# ModularLight.net
KiCad netlist of a schematic drawn in EAGLE
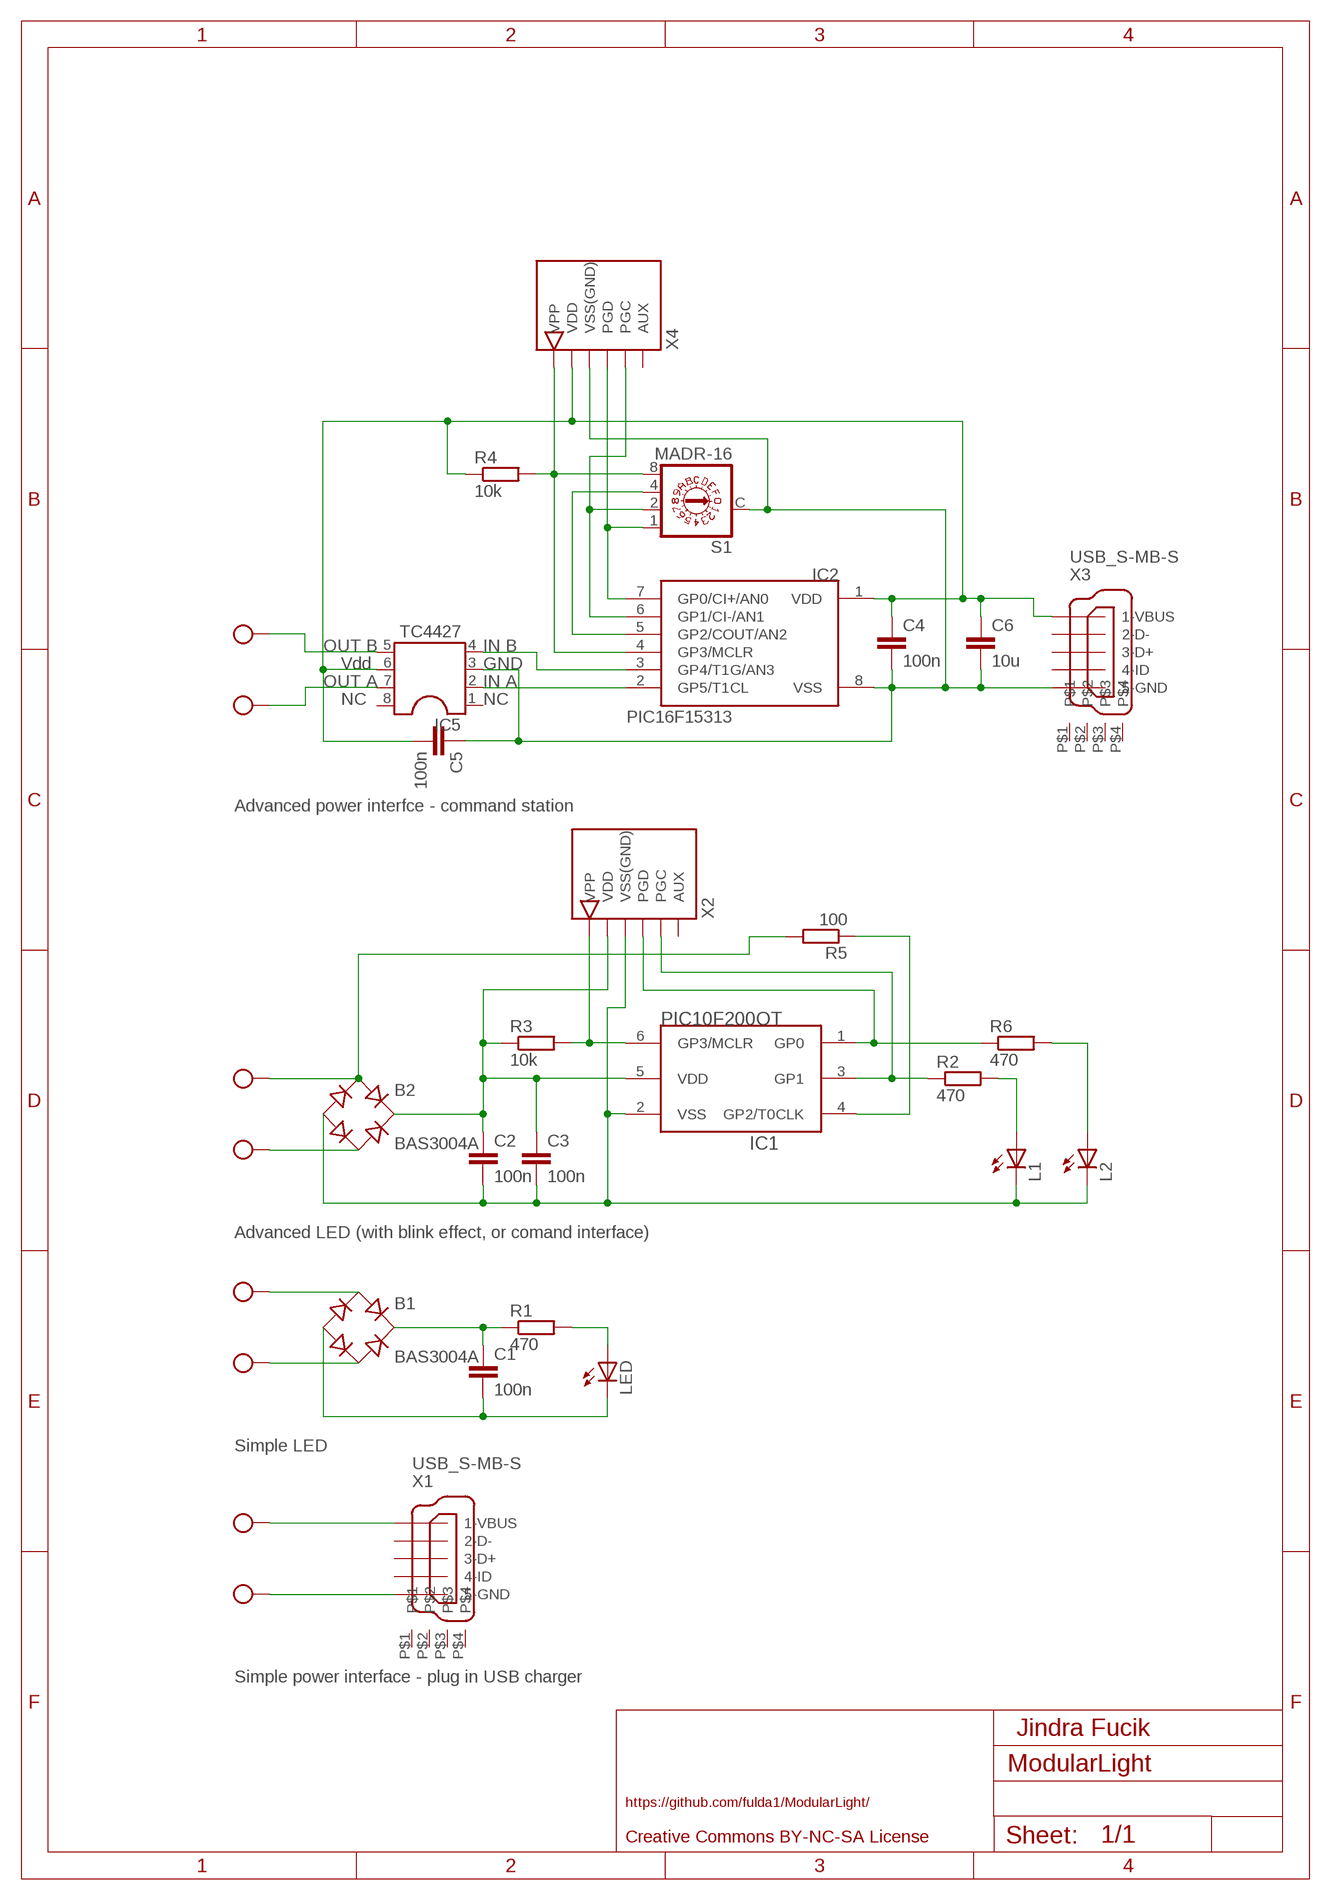
[diagram p0: schematic, sheet 1]

(export (version "E")
  (design (tool "Eeschema 10.0.6"))
  (components
    (comp (ref "B1")
      (value "BAS3004A")
      (footprint "eagle-import:SOT143")
      (libsource (lib "eagle-import") (part "RECTIFIER-SOT143"))
    )
    (comp (ref "B2")
      (value "BAS3004A")
      (footprint "eagle-import:SOT143")
      (libsource (lib "eagle-import") (part "RECTIFIER-SOT143"))
    )
    (comp (ref "C1")
      (value "100n")
      (footprint "eagle-import:C0805")
      (libsource (lib "eagle-import") (part "C-EUC0805"))
    )
    (comp (ref "C2")
      (value "100n")
      (footprint "eagle-import:C0805")
      (libsource (lib "eagle-import") (part "C-EUC0805"))
    )
    (comp (ref "C3")
      (value "100n")
      (footprint "eagle-import:C0805")
      (libsource (lib "eagle-import") (part "C-EUC0805"))
    )
    (comp (ref "C4")
      (value "100n")
      (footprint "eagle-import:C0805")
      (libsource (lib "eagle-import") (part "C-EUC0805"))
    )
    (comp (ref "C5")
      (value "100n")
      (footprint "eagle-import:C0805")
      (libsource (lib "eagle-import") (part "C-EUC0805"))
    )
    (comp (ref "C6")
      (value "10u")
      (footprint "eagle-import:C0805")
      (libsource (lib "eagle-import") (part "C-EUC0805"))
    )
    (comp (ref "IC1")
      (value "PIC10F200OT")
      (footprint "eagle-import:SOT23-6")
      (libsource (lib "eagle-import") (part "PIC10F20OT0"))
    )
    (comp (ref "IC2")
      (value "PIC16F15313")
      (footprint "eagle-import:SO-08")
      (libsource (lib "eagle-import") (part "PIC12F6SN29"))
    )
    (comp (ref "IC5")
      (value "TC4427")
      (footprint "eagle-import:SO-08")
      (libsource (lib "eagle-import") (part "SO-08"))
    )
    (comp (ref "J1")
      (value "PINHEAD_B")
      (footprint "eagle-import:2PIN_L")
      (libsource (lib "eagle-import") (part "PINHEAD_B"))
    )
    (comp (ref "J2")
      (value "PINHEAD_B")
      (footprint "eagle-import:2PIN_L")
      (libsource (lib "eagle-import") (part "PINHEAD_B"))
    )
    (comp (ref "J3")
      (value "PINHEAD_B")
      (footprint "eagle-import:2PIN_L")
      (libsource (lib "eagle-import") (part "PINHEAD_B"))
    )
    (comp (ref "J4")
      (value "PINHEAD_B")
      (footprint "eagle-import:2PIN_L")
      (libsource (lib "eagle-import") (part "PINHEAD_B"))
    )
    (comp (ref "L1")
      (value "LED3MM_I")
      (footprint "eagle-import:LED3MM_I")
      (libsource (lib "eagle-import") (part "LED3MM_I"))
    )
    (comp (ref "L2")
      (value "LED3MM_I")
      (footprint "eagle-import:LED3MM_I")
      (libsource (lib "eagle-import") (part "LED3MM_I"))
    )
    (comp (ref "LED")
      (value "LED3MM_I")
      (footprint "eagle-import:LED3MM_I")
      (libsource (lib "eagle-import") (part "LED3MM_I"))
    )
    (comp (ref "R1")
      (value "470")
      (footprint "eagle-import:R0805")
      (libsource (lib "eagle-import") (part "R-EU_R0805"))
    )
    (comp (ref "R2")
      (value "470")
      (footprint "eagle-import:R0805")
      (libsource (lib "eagle-import") (part "R-EU_R0805"))
    )
    (comp (ref "R3")
      (value "10k")
      (footprint "eagle-import:R0805")
      (libsource (lib "eagle-import") (part "R-EU_R0805"))
    )
    (comp (ref "R4")
      (value "10k")
      (footprint "eagle-import:R0805")
      (libsource (lib "eagle-import") (part "R-EU_R0805"))
    )
    (comp (ref "R5")
      (value "100")
      (footprint "eagle-import:R0805")
      (libsource (lib "eagle-import") (part "R-EU_R0805"))
    )
    (comp (ref "R6")
      (value "470")
      (footprint "eagle-import:R0805")
      (libsource (lib "eagle-import") (part "R-EU_R0805"))
    )
    (comp (ref "S1")
      (value "MADR-16")
      (footprint "eagle-import:P103")
      (libsource (lib "eagle-import") (part "P103"))
    )
    (comp (ref "X1")
      (value "USB_S-MB-S")
      (footprint "eagle-import:USB-MB-S")
      (libsource (lib "eagle-import") (part "USB_S-MB-S"))
    )
    (comp (ref "X2")
      (value "PICKITXS")
      (footprint "eagle-import:6PIN3")
      (libsource (lib "eagle-import") (part "PICKITXS"))
    )
    (comp (ref "X3")
      (value "USB_S-MB-S")
      (footprint "eagle-import:USB-MB-S")
      (libsource (lib "eagle-import") (part "USB_S-MB-S"))
    )
    (comp (ref "X4")
      (value "PICKITXS")
      (footprint "eagle-import:6PIN3")
      (libsource (lib "eagle-import") (part "PICKITXS"))
    )
  )
  (nets
    (net (code "1") (name "Net-(B1-+)") (class "Default")
      (node (ref "B1") (pin "4") (pinfunction "+_4") (pintype "passive"))
      (node (ref "C1") (pin "1") (pinfunction "1_1") (pintype "passive"))
      (node (ref "R1") (pin "1") (pinfunction "1_1") (pintype "passive"))
    )
    (net (code "2") (name "Net-(B1--)") (class "Default")
      (node (ref "B1") (pin "1") (pinfunction "-_1") (pintype "passive"))
      (node (ref "C1") (pin "2") (pinfunction "2_2") (pintype "passive"))
      (node (ref "LED") (pin "K") (pinfunction "C_K") (pintype "passive"))
    )
    (net (code "3") (name "Net-(B1-AC1)") (class "Default")
      (node (ref "B1") (pin "2") (pinfunction "AC1_2") (pintype "passive"))
      (node (ref "J2") (pin "1") (pinfunction "P$1_1") (pintype "bidirectional"))
    )
    (net (code "4") (name "Net-(B1-AC2)") (class "Default")
      (node (ref "B1") (pin "3") (pinfunction "AC2_3") (pintype "passive"))
      (node (ref "J2") (pin "2") (pinfunction "P$1_2") (pintype "bidirectional"))
    )
    (net (code "5") (name "Net-(B2-+)") (class "Default")
      (node (ref "B2") (pin "4") (pinfunction "+_4") (pintype "passive"))
      (node (ref "C2") (pin "1") (pinfunction "1_1") (pintype "passive"))
      (node (ref "C3") (pin "1") (pinfunction "1_1") (pintype "passive"))
      (node (ref "IC1") (pin "5") (pinfunction "VDD_5") (pintype "power_in"))
      (node (ref "R3") (pin "1") (pinfunction "1_1") (pintype "passive"))
      (node (ref "X2") (pin "P$2") (pinfunction "VDD_P$2") (pintype "bidirectional"))
    )
    (net (code "6") (name "Net-(B2--)") (class "Default")
      (node (ref "B2") (pin "1") (pinfunction "-_1") (pintype "passive"))
      (node (ref "C2") (pin "2") (pinfunction "2_2") (pintype "passive"))
      (node (ref "C3") (pin "2") (pinfunction "2_2") (pintype "passive"))
      (node (ref "IC1") (pin "2") (pinfunction "VSS_2") (pintype "power_in"))
      (node (ref "L1") (pin "K") (pinfunction "C_K") (pintype "passive"))
      (node (ref "L2") (pin "K") (pinfunction "C_K") (pintype "passive"))
      (node (ref "X2") (pin "P$3") (pinfunction "VSS(GND)_P$3") (pintype "bidirectional"))
    )
    (net (code "7") (name "Net-(B2-AC1)") (class "Default")
      (node (ref "B2") (pin "2") (pinfunction "AC1_2") (pintype "passive"))
      (node (ref "J3") (pin "1") (pinfunction "P$1_1") (pintype "bidirectional"))
      (node (ref "R5") (pin "2") (pinfunction "2_2") (pintype "passive"))
    )
    (net (code "8") (name "Net-(B2-AC2)") (class "Default")
      (node (ref "B2") (pin "3") (pinfunction "AC2_3") (pintype "passive"))
      (node (ref "J3") (pin "2") (pinfunction "P$1_2") (pintype "bidirectional"))
    )
    (net (code "9") (name "Net-(IC1-GP0)") (class "Default")
      (node (ref "IC1") (pin "1") (pinfunction "GP0_1") (pintype "bidirectional"))
      (node (ref "R6") (pin "1") (pinfunction "1_1") (pintype "passive"))
      (node (ref "X2") (pin "P$4") (pinfunction "PGD_P$4") (pintype "bidirectional"))
    )
    (net (code "10") (name "Net-(IC1-GP1)") (class "Default")
      (node (ref "IC1") (pin "3") (pinfunction "GP1_3") (pintype "bidirectional"))
      (node (ref "R2") (pin "1") (pinfunction "1_1") (pintype "passive"))
      (node (ref "X2") (pin "P$5") (pinfunction "PGC_P$5") (pintype "bidirectional"))
    )
    (net (code "11") (name "Net-(IC1-GP2{slash}T0CLK)") (class "Default")
      (node (ref "IC1") (pin "4") (pinfunction "GP2/T0CLK_4") (pintype "bidirectional"))
      (node (ref "R5") (pin "1") (pinfunction "1_1") (pintype "passive"))
    )
    (net (code "12") (name "Net-(IC1-GP3{slash}MCLR)") (class "Default")
      (node (ref "IC1") (pin "6") (pinfunction "GP3/MCLR_6") (pintype "input"))
      (node (ref "R3") (pin "2") (pinfunction "2_2") (pintype "passive"))
      (node (ref "X2") (pin "P$1") (pinfunction "VPP_P$1") (pintype "bidirectional"))
    )
    (net (code "13") (name "Net-(IC2-GP0{slash}CI+{slash}AN0)") (class "Default")
      (node (ref "IC2") (pin "7") (pinfunction "GP0/CI+/AN0_7") (pintype "bidirectional"))
      (node (ref "S1") (pin "1") (pinfunction "1_1") (pintype "passive"))
      (node (ref "X4") (pin "P$4") (pinfunction "PGD_P$4") (pintype "bidirectional"))
    )
    (net (code "14") (name "Net-(IC2-GP1{slash}CI-{slash}AN1)") (class "Default")
      (node (ref "IC2") (pin "6") (pinfunction "GP1/CI-/AN1_6") (pintype "bidirectional"))
      (node (ref "S1") (pin "2") (pinfunction "2_2") (pintype "passive"))
      (node (ref "X4") (pin "P$5") (pinfunction "PGC_P$5") (pintype "bidirectional"))
    )
    (net (code "15") (name "Net-(IC2-GP2{slash}COUT{slash}AN2)") (class "Default")
      (node (ref "IC2") (pin "5") (pinfunction "GP2/COUT/AN2_5") (pintype "bidirectional"))
      (node (ref "S1") (pin "4") (pinfunction "4_4") (pintype "passive"))
    )
    (net (code "16") (name "Net-(IC2-GP3{slash}MCLR)") (class "Default")
      (node (ref "IC2") (pin "4") (pinfunction "GP3/MCLR_4") (pintype "input"))
      (node (ref "R4") (pin "2") (pinfunction "2_2") (pintype "passive"))
      (node (ref "S1") (pin "8") (pinfunction "8_8") (pintype "passive"))
      (node (ref "X4") (pin "P$1") (pinfunction "VPP_P$1") (pintype "bidirectional"))
    )
    (net (code "17") (name "Net-(IC2-GP4{slash}T1G{slash}AN3)") (class "Default")
      (node (ref "IC2") (pin "3") (pinfunction "GP4/T1G/AN3_3") (pintype "bidirectional"))
      (node (ref "IC5") (pin "4") (pinfunction "4_4") (pintype "passive"))
    )
    (net (code "18") (name "Net-(IC2-GP5{slash}T1CL)") (class "Default")
      (node (ref "IC2") (pin "2") (pinfunction "GP5/T1CL_2") (pintype "bidirectional"))
      (node (ref "IC5") (pin "2") (pinfunction "2_2") (pintype "passive"))
    )
    (net (code "19") (name "Net-(IC2-VDD)") (class "Default")
      (node (ref "C4") (pin "1") (pinfunction "1_1") (pintype "passive"))
      (node (ref "C5") (pin "2") (pinfunction "2_2") (pintype "passive"))
      (node (ref "C6") (pin "1") (pinfunction "1_1") (pintype "passive"))
      (node (ref "IC2") (pin "1") (pinfunction "VDD_1") (pintype "power_in"))
      (node (ref "IC5") (pin "6") (pinfunction "6_6") (pintype "passive"))
      (node (ref "R4") (pin "1") (pinfunction "1_1") (pintype "passive"))
      (node (ref "X3") (pin "VBUS") (pinfunction "1-VBUS_VBUS") (pintype "input"))
      (node (ref "X4") (pin "P$2") (pinfunction "VDD_P$2") (pintype "bidirectional"))
    )
    (net (code "20") (name "Net-(IC2-VSS)") (class "Default")
      (node (ref "C4") (pin "2") (pinfunction "2_2") (pintype "passive"))
      (node (ref "C5") (pin "1") (pinfunction "1_1") (pintype "passive"))
      (node (ref "C6") (pin "2") (pinfunction "2_2") (pintype "passive"))
      (node (ref "IC2") (pin "8") (pinfunction "VSS_8") (pintype "power_in"))
      (node (ref "IC5") (pin "3") (pinfunction "3_3") (pintype "passive"))
      (node (ref "S1") (pin "C") (pinfunction "C_C") (pintype "passive"))
      (node (ref "X3") (pin "GND") (pinfunction "5-GND_GND") (pintype "input"))
      (node (ref "X4") (pin "P$3") (pinfunction "VSS(GND)_P$3") (pintype "bidirectional"))
    )
    (net (code "21") (name "Net-(J1A-P$1)") (class "Default")
      (node (ref "J1") (pin "1") (pinfunction "P$1_1") (pintype "bidirectional"))
      (node (ref "X1") (pin "VBUS") (pinfunction "1-VBUS_VBUS") (pintype "input"))
    )
    (net (code "22") (name "Net-(J1B-P$1)") (class "Default")
      (node (ref "J1") (pin "2") (pinfunction "P$1_2") (pintype "bidirectional"))
      (node (ref "X1") (pin "GND") (pinfunction "5-GND_GND") (pintype "input"))
    )
    (net (code "23") (name "Net-(J4A-P$1)") (class "Default")
      (node (ref "IC5") (pin "5") (pinfunction "5_5") (pintype "passive"))
      (node (ref "J4") (pin "1") (pinfunction "P$1_1") (pintype "bidirectional"))
    )
    (net (code "24") (name "Net-(J4B-P$1)") (class "Default")
      (node (ref "IC5") (pin "7") (pinfunction "7_7") (pintype "passive"))
      (node (ref "J4") (pin "2") (pinfunction "P$1_2") (pintype "bidirectional"))
    )
    (net (code "25") (name "Net-(L1-PadA)") (class "Default")
      (node (ref "L1") (pin "A") (pinfunction "A_A") (pintype "passive"))
      (node (ref "R2") (pin "2") (pinfunction "2_2") (pintype "passive"))
    )
    (net (code "26") (name "Net-(L2-PadA)") (class "Default")
      (node (ref "L2") (pin "A") (pinfunction "A_A") (pintype "passive"))
      (node (ref "R6") (pin "2") (pinfunction "2_2") (pintype "passive"))
    )
    (net (code "27") (name "Net-(LED-PadA)") (class "Default")
      (node (ref "LED") (pin "A") (pinfunction "A_A") (pintype "passive"))
      (node (ref "R1") (pin "2") (pinfunction "2_2") (pintype "passive"))
    )
    (net (code "28") (name "unconnected-(IC5-Pad1)") (class "Default")
      (node (ref "IC5") (pin "1") (pinfunction "1_1") (pintype "passive"))
    )
    (net (code "29") (name "unconnected-(IC5-Pad8)") (class "Default")
      (node (ref "IC5") (pin "8") (pinfunction "8_8") (pintype "passive"))
    )
    (net (code "30") (name "unconnected-(X1-2-D--PadD-)") (class "Default")
      (node (ref "X1") (pin "D-") (pinfunction "2-D-_D-") (pintype "input"))
    )
    (net (code "31") (name "unconnected-(X1-3-D+-PadD+)") (class "Default")
      (node (ref "X1") (pin "D+") (pinfunction "3-D+_D+") (pintype "input"))
    )
    (net (code "32") (name "unconnected-(X1-4-ID-PadID)") (class "Default")
      (node (ref "X1") (pin "ID") (pinfunction "4-ID_ID") (pintype "input"))
    )
    (net (code "33") (name "unconnected-(X1-PadP$1)") (class "Default")
      (node (ref "X1") (pin "P$1") (pinfunction "P$1_P$1") (pintype "passive"))
    )
    (net (code "34") (name "unconnected-(X1-PadP$2)") (class "Default")
      (node (ref "X1") (pin "P$2") (pinfunction "P$2_P$2") (pintype "passive"))
    )
    (net (code "35") (name "unconnected-(X1-PadP$3)") (class "Default")
      (node (ref "X1") (pin "P$3") (pinfunction "P$3_P$3") (pintype "passive"))
    )
    (net (code "36") (name "unconnected-(X1-PadP$4)") (class "Default")
      (node (ref "X1") (pin "P$4") (pinfunction "P$4_P$4") (pintype "passive"))
    )
    (net (code "37") (name "unconnected-(X2-AUX-PadP$6)") (class "Default")
      (node (ref "X2") (pin "P$6") (pinfunction "AUX_P$6") (pintype "bidirectional"))
    )
    (net (code "38") (name "unconnected-(X3-2-D--PadD-)") (class "Default")
      (node (ref "X3") (pin "D-") (pinfunction "2-D-_D-") (pintype "input"))
    )
    (net (code "39") (name "unconnected-(X3-3-D+-PadD+)") (class "Default")
      (node (ref "X3") (pin "D+") (pinfunction "3-D+_D+") (pintype "input"))
    )
    (net (code "40") (name "unconnected-(X3-4-ID-PadID)") (class "Default")
      (node (ref "X3") (pin "ID") (pinfunction "4-ID_ID") (pintype "input"))
    )
    (net (code "41") (name "unconnected-(X3-PadP$1)") (class "Default")
      (node (ref "X3") (pin "P$1") (pinfunction "P$1_P$1") (pintype "passive"))
    )
    (net (code "42") (name "unconnected-(X3-PadP$2)") (class "Default")
      (node (ref "X3") (pin "P$2") (pinfunction "P$2_P$2") (pintype "passive"))
    )
    (net (code "43") (name "unconnected-(X3-PadP$3)") (class "Default")
      (node (ref "X3") (pin "P$3") (pinfunction "P$3_P$3") (pintype "passive"))
    )
    (net (code "44") (name "unconnected-(X3-PadP$4)") (class "Default")
      (node (ref "X3") (pin "P$4") (pinfunction "P$4_P$4") (pintype "passive"))
    )
    (net (code "45") (name "unconnected-(X4-AUX-PadP$6)") (class "Default")
      (node (ref "X4") (pin "P$6") (pinfunction "AUX_P$6") (pintype "bidirectional"))
    )
  )
)
